# DCDC_combined.net
KiCad netlist of a schematic drawn in EAGLE
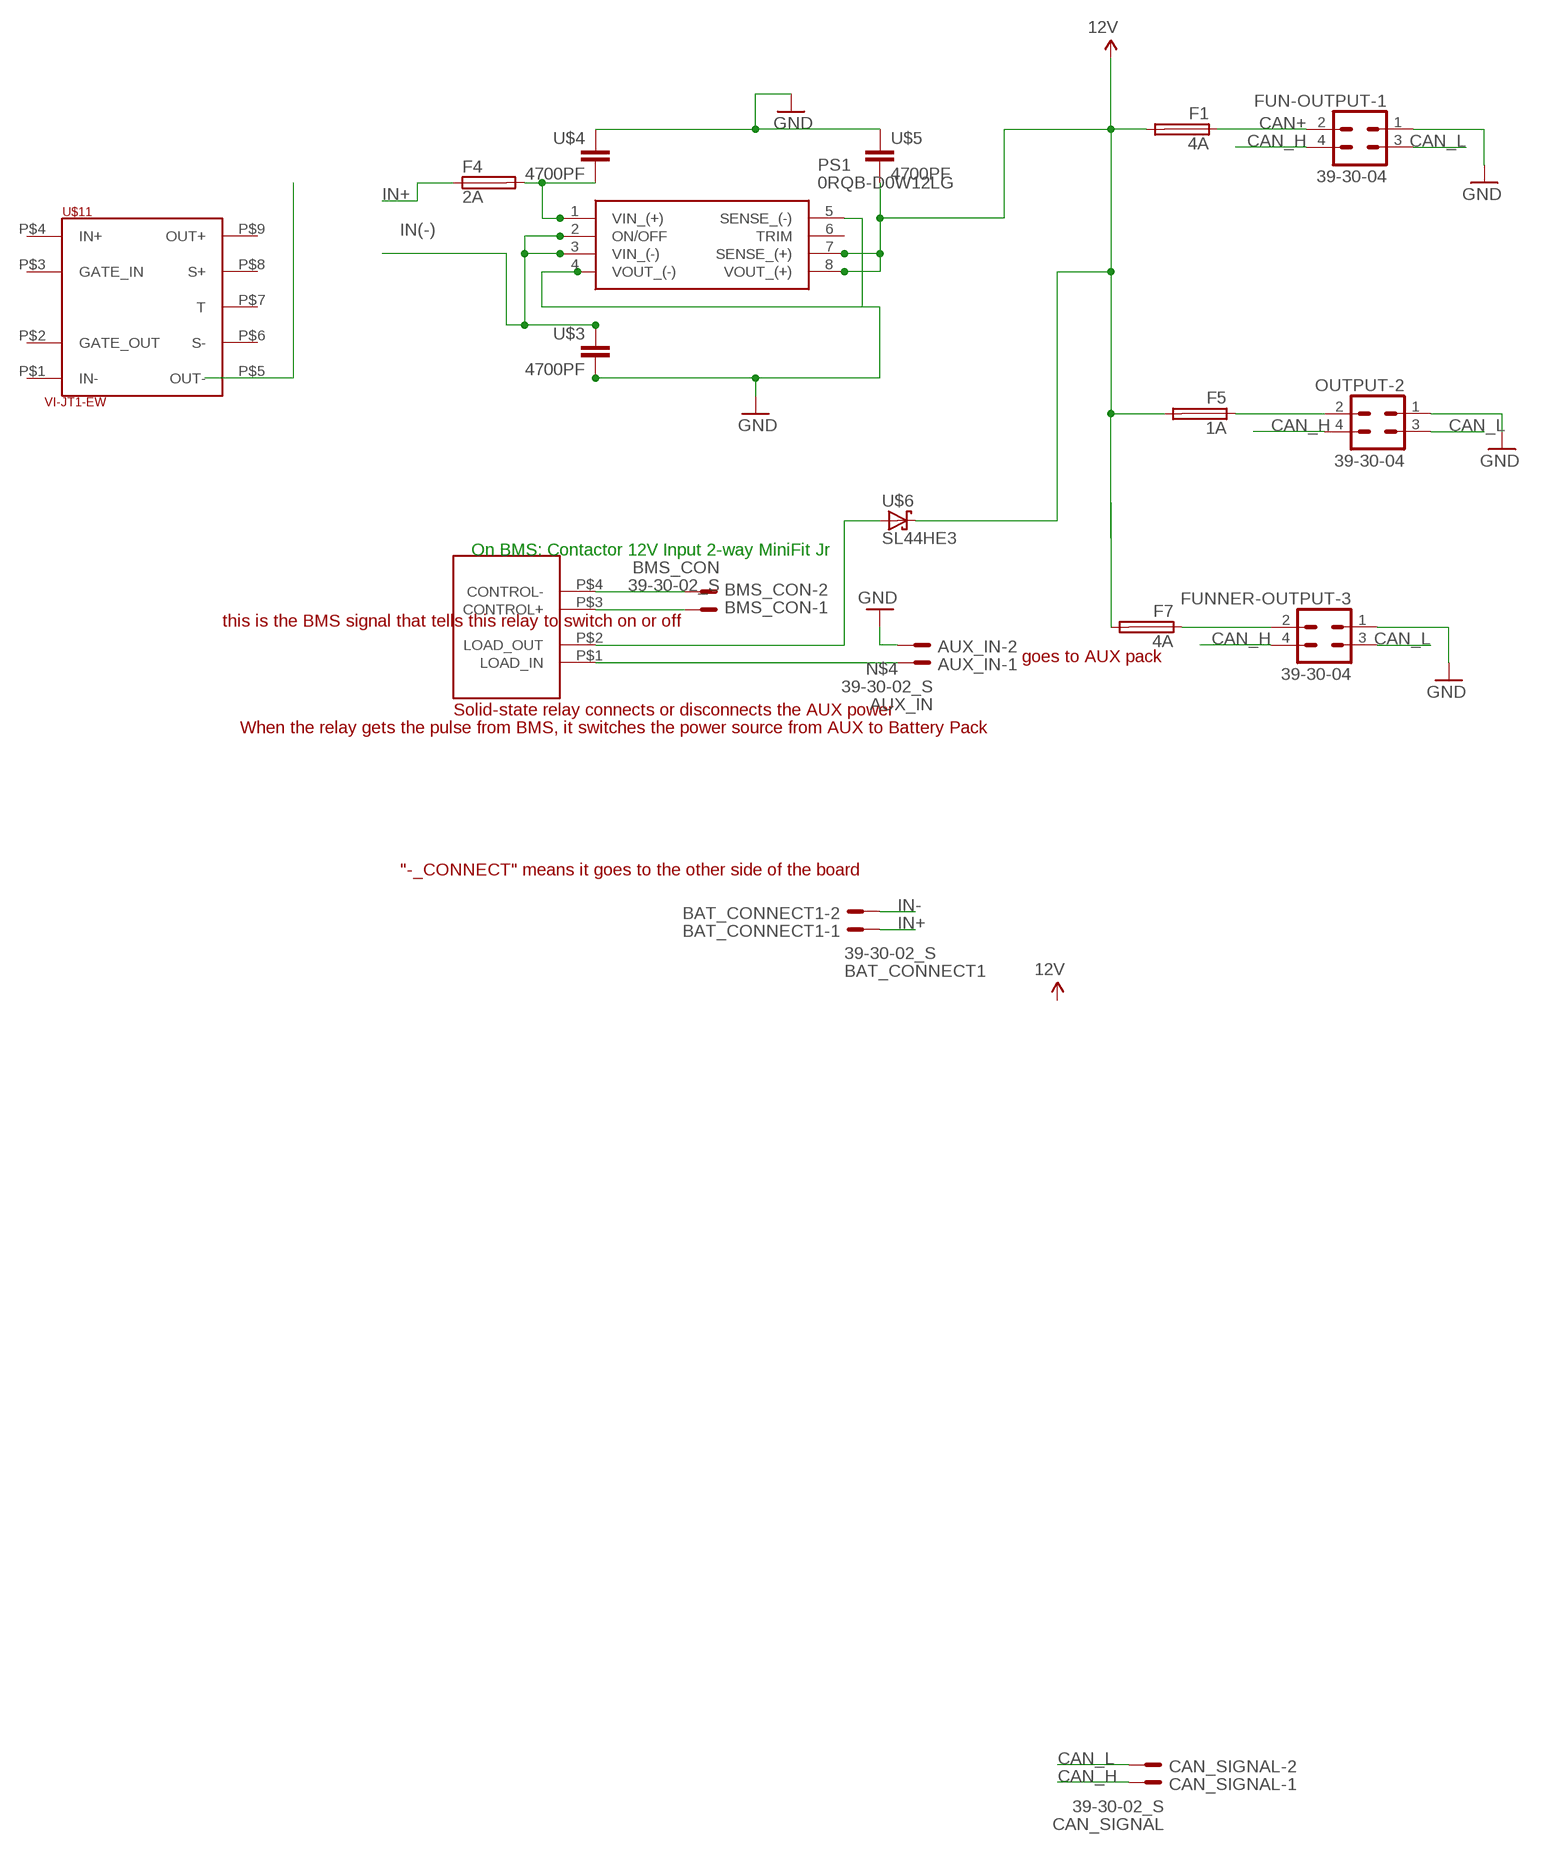
[diagram p0: schematic, sheet 1]

(export (version "E")
  (design (tool "Eeschema 10.0.6"))
  (components
    (comp (ref "AUX_IN")
      (value "39-30-02_S")
      (footprint "eagle-import:39-30-_02_")
      (libsource (lib "eagle-import") (part "39-30-?02?_S"))
    )
    (comp (ref "BAT_CONNECT1")
      (value "39-30-02_S")
      (footprint "eagle-import:39-30-_02_")
      (libsource (lib "eagle-import") (part "39-30-?02?_S"))
    )
    (comp (ref "BMS_CON")
      (value "39-30-02_S")
      (footprint "eagle-import:39-30-_02_")
      (libsource (lib "eagle-import") (part "39-30-?02?_S"))
    )
    (comp (ref "CAN_SIGNAL")
      (value "39-30-02_S")
      (footprint "eagle-import:39-30-_02_")
      (libsource (lib "eagle-import") (part "39-30-?02?_S"))
    )
    (comp (ref "F1")
      (value "4A")
      (footprint "eagle-import:OMNIBLOK")
      (libsource (lib "eagle-import") (part "SMD-MICRO-FUSE-BLOCK"))
    )
    (comp (ref "F4")
      (value "2A")
      (footprint "eagle-import:OMNIBLOK")
      (libsource (lib "eagle-import") (part "SMD-MICRO-FUSE-BLOCK"))
    )
    (comp (ref "F5")
      (value "1A")
      (footprint "eagle-import:OMNIBLOK")
      (libsource (lib "eagle-import") (part "SMD-MICRO-FUSE-BLOCK"))
    )
    (comp (ref "F7")
      (value "4A")
      (footprint "eagle-import:OMNIBLOK")
      (libsource (lib "eagle-import") (part "SMD-MICRO-FUSE-BLOCK"))
    )
    (comp (ref "FUN-OUTPUT-1")
      (value "39-30-04")
      (footprint "eagle-import:39-30-_04_")
      (libsource (lib "eagle-import") (part "39-30-?04?"))
    )
    (comp (ref "FUNNER-OUTPUT-3")
      (value "39-30-04")
      (footprint "eagle-import:39-30-_04_")
      (libsource (lib "eagle-import") (part "39-30-?04?"))
    )
    (comp (ref "OUTPUT-2")
      (value "39-30-04")
      (footprint "eagle-import:39-30-_04_")
      (libsource (lib "eagle-import") (part "39-30-?04?"))
    )
    (comp (ref "PS1")
      (value "0RQB-D0W12LG")
      (footprint "eagle-import:0RQBD0W12LG")
      (libsource (lib "eagle-import") (part "0RQB-D0W12LG"))
    )
    (comp (ref "U$2")
      (value "MPDCD3B")
      (footprint "eagle-import:MPDCD3B")
      (libsource (lib "eagle-import") (part "MPDCD3B"))
    )
    (comp (ref "U$3")
      (value "4700PF")
      (footprint "eagle-import:Y2_CAP")
      (libsource (lib "eagle-import") (part "4700PF"))
    )
    (comp (ref "U$4")
      (value "4700PF")
      (footprint "eagle-import:Y2_CAP")
      (libsource (lib "eagle-import") (part "4700PF"))
    )
    (comp (ref "U$5")
      (value "4700PF")
      (footprint "eagle-import:Y2_CAP")
      (libsource (lib "eagle-import") (part "4700PF"))
    )
    (comp (ref "U$6")
      (value "SL44HE3")
      (footprint "eagle-import:SMC")
      (libsource (lib "eagle-import") (part "SL44HE3"))
    )
    (comp (ref "U$11")
      (value "VI-JT1-EW")
      (footprint "eagle-import:VI-J00")
      (libsource (lib "eagle-import") (part "VI-JT1-EW"))
    )
  )
  (nets
    (net (code "1") (name "/CAN+") (class "Default")
      (node (ref "F1") (pin "P$1") (pinfunction "1_P$1") (pintype "passive"))
      (node (ref "FUN-OUTPUT-1") (pin "2") (pinfunction "2_2") (pintype "passive"))
    )
    (net (code "2") (name "/CAN_H") (class "Default")
      (node (ref "CAN_SIGNAL") (pin "1") (pinfunction "P_1") (pintype "passive"))
      (node (ref "FUN-OUTPUT-1") (pin "4") (pinfunction "4_4") (pintype "passive"))
      (node (ref "FUNNER-OUTPUT-3") (pin "4") (pinfunction "4_4") (pintype "passive"))
      (node (ref "OUTPUT-2") (pin "4") (pinfunction "4_4") (pintype "passive"))
    )
    (net (code "3") (name "/CAN_L") (class "Default")
      (node (ref "CAN_SIGNAL") (pin "2") (pinfunction "P_2") (pintype "passive"))
      (node (ref "FUN-OUTPUT-1") (pin "3") (pinfunction "3_3") (pintype "passive"))
      (node (ref "FUNNER-OUTPUT-3") (pin "3") (pinfunction "3_3") (pintype "passive"))
      (node (ref "OUTPUT-2") (pin "3") (pinfunction "3_3") (pintype "passive"))
    )
    (net (code "4") (name "/IN(-)") (class "Default")
      (node (ref "PS1") (pin "2") (pinfunction "ON/OFF_2") (pintype "bidirectional"))
      (node (ref "PS1") (pin "3") (pinfunction "VIN_(-)_3") (pintype "bidirectional"))
      (node (ref "U$3") (pin "P$1") (pinfunction "1_P$1") (pintype "passive"))
    )
    (net (code "5") (name "/IN+") (class "Default")
      (node (ref "BAT_CONNECT1") (pin "1") (pinfunction "P_1") (pintype "passive"))
      (node (ref "F4") (pin "P$1") (pinfunction "1_P$1") (pintype "passive"))
    )
    (net (code "6") (name "/IN-") (class "Default")
      (node (ref "BAT_CONNECT1") (pin "2") (pinfunction "P_2") (pintype "passive"))
    )
    (net (code "7") (name "/N$4") (class "Default")
      (node (ref "BMS_CON") (pin "2") (pinfunction "P_2") (pintype "passive"))
      (node (ref "U$2") (pin "P$2") (pinfunction "LOAD_OUT_P$2") (pintype "bidirectional"))
      (node (ref "U$2") (pin "P$4") (pinfunction "CONTROL-_P$4") (pintype "bidirectional"))
      (node (ref "U$6") (pin "A") (pinfunction "A_A") (pintype "passive"))
    )
    (net (code "8") (name "12V") (class "Default")
      (node (ref "F1") (pin "P$2") (pinfunction "2_P$2") (pintype "passive"))
      (node (ref "F5") (pin "P$2") (pinfunction "2_P$2") (pintype "passive"))
      (node (ref "PS1") (pin "7") (pinfunction "SENSE_(+)_7") (pintype "bidirectional"))
      (node (ref "PS1") (pin "8") (pinfunction "VOUT_(+)_8") (pintype "bidirectional"))
      (node (ref "U$5") (pin "P$2") (pinfunction "2_P$2") (pintype "passive"))
      (node (ref "U$6") (pin "C") (pinfunction "C_C") (pintype "passive"))
    )
    (net (code "9") (name "GND") (class "Default")
      (node (ref "AUX_IN") (pin "2") (pinfunction "P_2") (pintype "passive"))
      (node (ref "FUN-OUTPUT-1") (pin "1") (pinfunction "1_1") (pintype "passive"))
      (node (ref "FUNNER-OUTPUT-3") (pin "1") (pinfunction "1_1") (pintype "passive"))
      (node (ref "OUTPUT-2") (pin "1") (pinfunction "1_1") (pintype "passive"))
      (node (ref "PS1") (pin "4") (pinfunction "VOUT_(-)_4") (pintype "bidirectional"))
      (node (ref "PS1") (pin "5") (pinfunction "SENSE_(-)_5") (pintype "bidirectional"))
      (node (ref "U$3") (pin "P$2") (pinfunction "2_P$2") (pintype "passive"))
      (node (ref "U$4") (pin "P$1") (pinfunction "1_P$1") (pintype "passive"))
      (node (ref "U$5") (pin "P$1") (pinfunction "1_P$1") (pintype "passive"))
    )
    (net (code "10") (name "Net-(AUX_INA-P)") (class "Default")
      (node (ref "AUX_IN") (pin "1") (pinfunction "P_1") (pintype "passive"))
      (node (ref "U$2") (pin "P$1") (pinfunction "LOAD_IN_P$1") (pintype "bidirectional"))
    )
    (net (code "11") (name "Net-(BMS_CONA-P)") (class "Default")
      (node (ref "BMS_CON") (pin "1") (pinfunction "P_1") (pintype "passive"))
      (node (ref "U$2") (pin "P$3") (pinfunction "CONTROL+_P$3") (pintype "bidirectional"))
    )
    (net (code "12") (name "Net-(F4-2)") (class "Default")
      (node (ref "F4") (pin "P$2") (pinfunction "2_P$2") (pintype "passive"))
      (node (ref "PS1") (pin "1") (pinfunction "VIN_(+)_1") (pintype "bidirectional"))
      (node (ref "U$4") (pin "P$2") (pinfunction "2_P$2") (pintype "passive"))
    )
    (net (code "13") (name "Net-(F5-1)") (class "Default")
      (node (ref "F5") (pin "P$1") (pinfunction "1_P$1") (pintype "passive"))
      (node (ref "OUTPUT-2") (pin "2") (pinfunction "2_2") (pintype "passive"))
    )
    (net (code "14") (name "Net-(F7-1)") (class "Default")
      (node (ref "F7") (pin "P$1") (pinfunction "1_P$1") (pintype "passive"))
      (node (ref "FUNNER-OUTPUT-3") (pin "2") (pinfunction "2_2") (pintype "passive"))
    )
    (net (code "15") (name "unconnected-(F7-2-PadP$2)") (class "Default")
      (node (ref "F7") (pin "P$2") (pinfunction "2_P$2") (pintype "passive"))
    )
    (net (code "16") (name "unconnected-(PS1-TRIM-Pad6)") (class "Default")
      (node (ref "PS1") (pin "6") (pinfunction "TRIM_6") (pintype "bidirectional"))
    )
    (net (code "17") (name "unconnected-(U$11-GATE_IN-PadP$3)") (class "Default")
      (node (ref "U$11") (pin "P$3") (pinfunction "GATE_IN_P$3") (pintype "bidirectional"))
    )
    (net (code "18") (name "unconnected-(U$11-GATE_OUT-PadP$2)") (class "Default")
      (node (ref "U$11") (pin "P$2") (pinfunction "GATE_OUT_P$2") (pintype "bidirectional"))
    )
    (net (code "19") (name "unconnected-(U$11-IN+-PadP$4)") (class "Default")
      (node (ref "U$11") (pin "P$4") (pinfunction "IN+_P$4") (pintype "bidirectional"))
    )
    (net (code "20") (name "unconnected-(U$11-IN--PadP$1)") (class "Default")
      (node (ref "U$11") (pin "P$1") (pinfunction "IN-_P$1") (pintype "bidirectional"))
    )
    (net (code "21") (name "unconnected-(U$11-OUT+-PadP$9)") (class "Default")
      (node (ref "U$11") (pin "P$9") (pinfunction "OUT+_P$9") (pintype "bidirectional"))
    )
    (net (code "22") (name "unconnected-(U$11-OUT--PadP$5)") (class "Default")
      (node (ref "U$11") (pin "P$5") (pinfunction "OUT-_P$5") (pintype "bidirectional"))
    )
    (net (code "23") (name "unconnected-(U$11-S+-PadP$8)") (class "Default")
      (node (ref "U$11") (pin "P$8") (pinfunction "S+_P$8") (pintype "bidirectional"))
    )
    (net (code "24") (name "unconnected-(U$11-S--PadP$6)") (class "Default")
      (node (ref "U$11") (pin "P$6") (pinfunction "S-_P$6") (pintype "bidirectional"))
    )
    (net (code "25") (name "unconnected-(U$11-T-PadP$7)") (class "Default")
      (node (ref "U$11") (pin "P$7") (pinfunction "T_P$7") (pintype "bidirectional"))
    )
  )
)
